# RelayController.net
KiCad netlist of a schematic drawn in Altium Designer
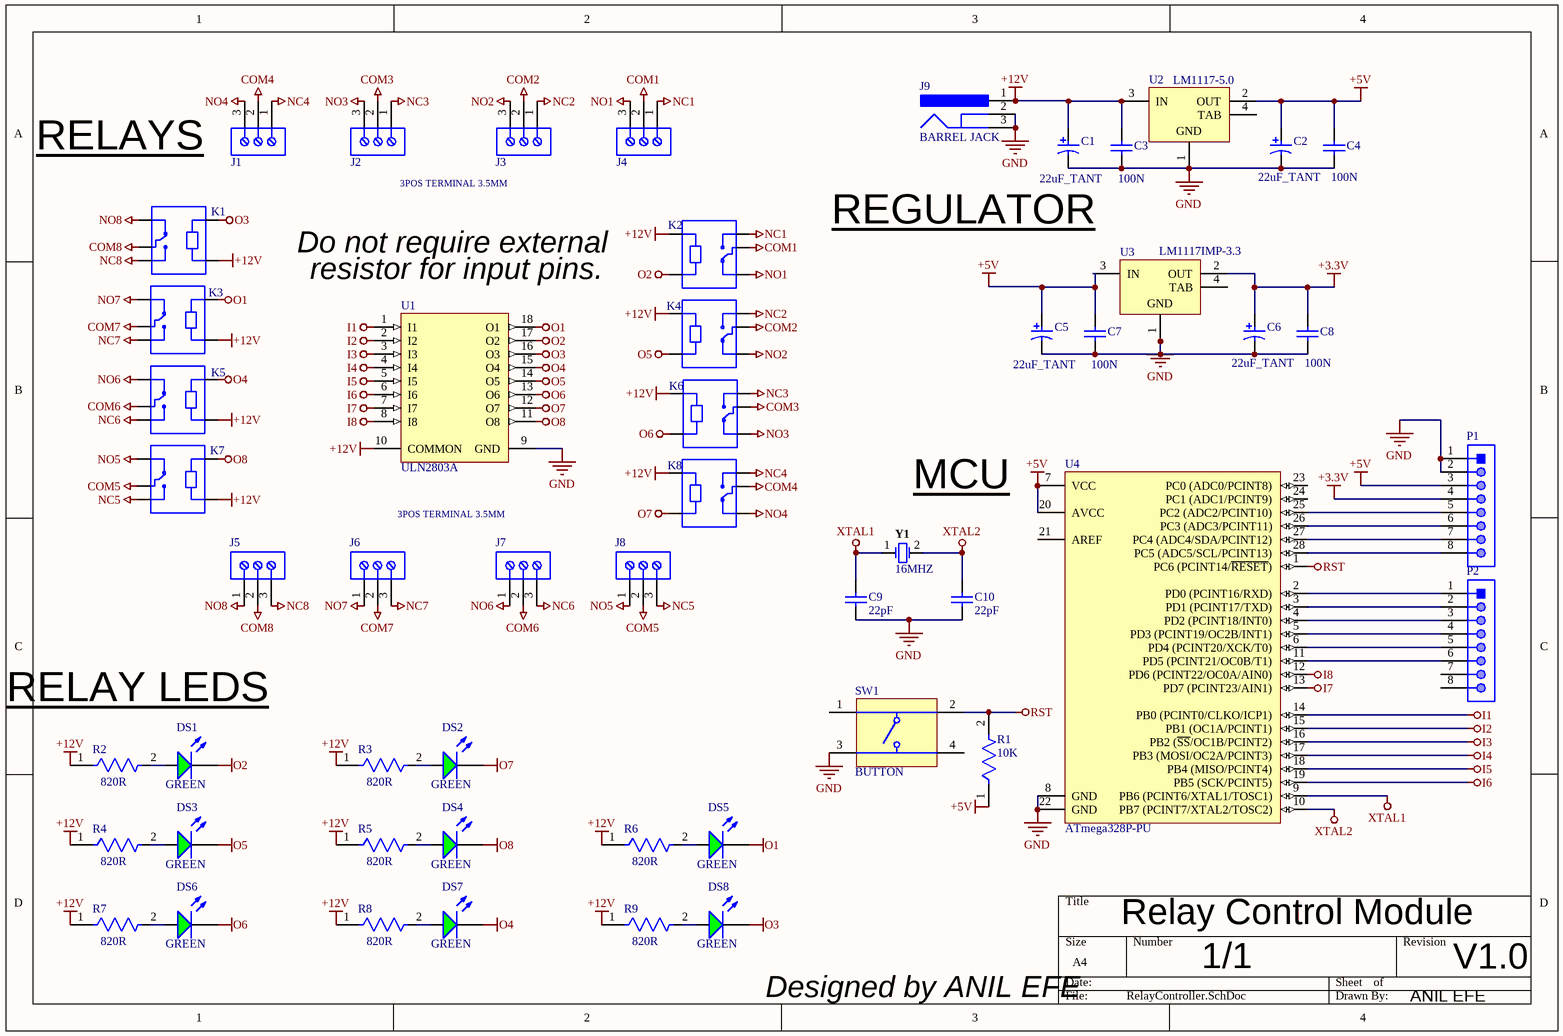
[diagram p0: RelayController.SchDoc]

(export (version "E")
  (design (tool "Eeschema 10.0.6"))
  (components
    (comp (ref "C1")
      (value "22uF_TANT")
      (footprint "KEMT-T491-D_L")
      (fields (field (name "MANUFACTURER") "Kemet"))
      (libsource (lib "Altium Content Vault") (part "CAP-P-2"))
    )
    (comp (ref "C2")
      (value "22uF_TANT")
      (footprint "KEMT-T491-D_L")
      (fields (field (name "MANUFACTURER") "Kemet"))
      (libsource (lib "Altium Content Vault") (part "CAP-P-2"))
    )
    (comp (ref "C3")
      (value "100N")
      (footprint "KEMT-1206-2_M")
      (description "CAP, Ceramic, 0.1 uF, +/- 10%, 50 V, -55 to 125 degC, 1206 (3216 Metric), RoHS, Tape and Reel")
      (fields (field (name "MANUFACTURER") "Kemet"))
      (libsource (lib "Altium Content Vault") (part "CAP-NP-2"))
    )
    (comp (ref "C4")
      (value "100N")
      (footprint "KEMT-1206-2_M")
      (description "CAP, Ceramic, 0.1 uF, +/- 10%, 50 V, -55 to 125 degC, 1206 (3216 Metric), RoHS, Tape and Reel")
      (fields (field (name "MANUFACTURER") "Kemet"))
      (libsource (lib "Altium Content Vault") (part "CAP-NP-2"))
    )
    (comp (ref "C5")
      (value "22uF_TANT")
      (footprint "KEMT-T491-D_L")
      (fields (field (name "MANUFACTURER") "Kemet"))
      (libsource (lib "Altium Content Vault") (part "CAP-P-2"))
    )
    (comp (ref "C6")
      (value "22uF_TANT")
      (footprint "KEMT-T491-D_L")
      (fields (field (name "MANUFACTURER") "Kemet"))
      (libsource (lib "Altium Content Vault") (part "CAP-P-2"))
    )
    (comp (ref "C7")
      (value "100N")
      (footprint "KEMT-1206-2_M")
      (description "CAP, Ceramic, 0.1 uF, +/- 10%, 50 V, -55 to 125 degC, 1206 (3216 Metric), RoHS, Tape and Reel")
      (fields (field (name "MANUFACTURER") "Kemet"))
      (libsource (lib "Altium Content Vault") (part "CAP-NP-2"))
    )
    (comp (ref "C8")
      (value "100N")
      (footprint "KEMT-1206-2_M")
      (description "CAP, Ceramic, 0.1 uF, +/- 10%, 50 V, -55 to 125 degC, 1206 (3216 Metric), RoHS, Tape and Reel")
      (fields (field (name "MANUFACTURER") "Kemet"))
      (libsource (lib "Altium Content Vault") (part "CAP-NP-2"))
    )
    (comp (ref "C9")
      (value "22pF")
      (footprint "KEMT-1206-2_M")
      (description "CAP, Ceramic, 0.1 uF, +/- 10%, 50 V, -55 to 125 degC, 1206 (3216 Metric), RoHS, Tape and Reel")
      (fields (field (name "MANUFACTURER") "Kemet"))
      (libsource (lib "Altium Content Vault") (part "CAP-NP-2"))
    )
    (comp (ref "C10")
      (value "22pF")
      (footprint "KEMT-1206-2_M")
      (description "CAP, Ceramic, 0.1 uF, +/- 10%, 50 V, -55 to 125 degC, 1206 (3216 Metric), RoHS, Tape and Reel")
      (fields (field (name "MANUFACTURER") "Kemet"))
      (libsource (lib "Altium Content Vault") (part "CAP-NP-2"))
    )
    (comp (ref "DS1")
      (value "GREEN")
      (footprint "KING-APTD3216CGCK_V")
      (description "Chip LED Lamp, Green, 5 V, 30 mA, -40 to 85 degC, 2-Pin SMD, RoHS, Tape and Reel")
      (fields (field (name "MANUFACTURER") "Kingbright"))
      (libsource (lib "Altium Content Vault") (part "LED-GREEN-AK-2"))
    )
    (comp (ref "DS2")
      (value "GREEN")
      (footprint "KING-APTD3216CGCK_V")
      (description "Chip LED Lamp, Green, 5 V, 30 mA, -40 to 85 degC, 2-Pin SMD, RoHS, Tape and Reel")
      (fields (field (name "MANUFACTURER") "Kingbright"))
      (libsource (lib "Altium Content Vault") (part "LED-GREEN-AK-2"))
    )
    (comp (ref "DS3")
      (value "GREEN")
      (footprint "KING-APTD3216CGCK_V")
      (description "Chip LED Lamp, Green, 5 V, 30 mA, -40 to 85 degC, 2-Pin SMD, RoHS, Tape and Reel")
      (fields (field (name "MANUFACTURER") "Kingbright"))
      (libsource (lib "Altium Content Vault") (part "LED-GREEN-AK-2"))
    )
    (comp (ref "DS4")
      (value "GREEN")
      (footprint "KING-APTD3216CGCK_V")
      (description "Chip LED Lamp, Green, 5 V, 30 mA, -40 to 85 degC, 2-Pin SMD, RoHS, Tape and Reel")
      (fields (field (name "MANUFACTURER") "Kingbright"))
      (libsource (lib "Altium Content Vault") (part "LED-GREEN-AK-2"))
    )
    (comp (ref "DS5")
      (value "GREEN")
      (footprint "KING-APTD3216CGCK_V")
      (description "Chip LED Lamp, Green, 5 V, 30 mA, -40 to 85 degC, 2-Pin SMD, RoHS, Tape and Reel")
      (fields (field (name "MANUFACTURER") "Kingbright"))
      (libsource (lib "Altium Content Vault") (part "LED-GREEN-AK-2"))
    )
    (comp (ref "DS6")
      (value "GREEN")
      (footprint "KING-APTD3216CGCK_V")
      (description "Chip LED Lamp, Green, 5 V, 30 mA, -40 to 85 degC, 2-Pin SMD, RoHS, Tape and Reel")
      (fields (field (name "MANUFACTURER") "Kingbright"))
      (libsource (lib "Altium Content Vault") (part "LED-GREEN-AK-2"))
    )
    (comp (ref "DS7")
      (value "GREEN")
      (footprint "KING-APTD3216CGCK_V")
      (description "Chip LED Lamp, Green, 5 V, 30 mA, -40 to 85 degC, 2-Pin SMD, RoHS, Tape and Reel")
      (fields (field (name "MANUFACTURER") "Kingbright"))
      (libsource (lib "Altium Content Vault") (part "LED-GREEN-AK-2"))
    )
    (comp (ref "DS8")
      (value "GREEN")
      (footprint "KING-APTD3216CGCK_V")
      (description "Chip LED Lamp, Green, 5 V, 30 mA, -40 to 85 degC, 2-Pin SMD, RoHS, Tape and Reel")
      (fields (field (name "MANUFACTURER") "Kingbright"))
      (libsource (lib "Altium Content Vault") (part "LED-GREEN-AK-2"))
    )
    (comp (ref "J1")
      (value "691214110003")
      (footprint "691214110003")
      (description "Serie 2141 - 3.50 mm Horizontal Entry Modular with Rising Cage Clamp WR-TBL, 3 pin")
      (fields (field (name "MANUFACTURER") "Wurth Elektronik") (field (name "PUBLISHER") "WurthElektronik"))
      (libsource (lib "Altium Content Vault") (part "WE-CN-1P-F-TB3"))
    )
    (comp (ref "J2")
      (value "691214110003")
      (footprint "691214110003")
      (description "Serie 2141 - 3.50 mm Horizontal Entry Modular with Rising Cage Clamp WR-TBL, 3 pin")
      (fields (field (name "MANUFACTURER") "Wurth Elektronik") (field (name "PUBLISHER") "WurthElektronik"))
      (libsource (lib "Altium Content Vault") (part "WE-CN-1P-F-TB3"))
    )
    (comp (ref "J3")
      (value "3POS TERMINAL 3.5MM")
      (footprint "691214110003")
      (description "Serie 2141 - 3.50 mm Horizontal Entry Modular with Rising Cage Clamp WR-TBL, 3 pin")
      (fields
        (field (name "MANUFACTURER") "Wurth Elektronik")
        (field (name "PART NUMBER") "691214110003")
        (field (name "PUBLISHER") "WurthElektronik")
      )
      (libsource (lib "Altium Content Vault") (part "WE-CN-1P-F-TB3"))
    )
    (comp (ref "J4")
      (value "691214110003")
      (footprint "691214110003")
      (description "Serie 2141 - 3.50 mm Horizontal Entry Modular with Rising Cage Clamp WR-TBL, 3 pin")
      (fields (field (name "MANUFACTURER") "Wurth Elektronik") (field (name "PUBLISHER") "WurthElektronik"))
      (libsource (lib "Altium Content Vault") (part "WE-CN-1P-F-TB3"))
    )
    (comp (ref "J5")
      (value "691214110003")
      (footprint "691214110003")
      (description "Serie 2141 - 3.50 mm Horizontal Entry Modular with Rising Cage Clamp WR-TBL, 3 pin")
      (fields (field (name "MANUFACTURER") "Wurth Elektronik") (field (name "PUBLISHER") "WurthElektronik"))
      (libsource (lib "Altium Content Vault") (part "WE-CN-1P-F-TB3"))
    )
    (comp (ref "J6")
      (value "3POS TERMINAL 3.5MM")
      (footprint "691214110003")
      (description "Serie 2141 - 3.50 mm Horizontal Entry Modular with Rising Cage Clamp WR-TBL, 3 pin")
      (fields
        (field (name "MANUFACTURER") "Wurth Elektronik")
        (field (name "PART NUMBER") "691214110003")
        (field (name "PUBLISHER") "WurthElektronik")
      )
      (libsource (lib "Altium Content Vault") (part "WE-CN-1P-F-TB3"))
    )
    (comp (ref "J7")
      (value "691214110003")
      (footprint "691214110003")
      (description "Serie 2141 - 3.50 mm Horizontal Entry Modular with Rising Cage Clamp WR-TBL, 3 pin")
      (fields (field (name "MANUFACTURER") "Wurth Elektronik") (field (name "PUBLISHER") "WurthElektronik"))
      (libsource (lib "Altium Content Vault") (part "WE-CN-1P-F-TB3"))
    )
    (comp (ref "J8")
      (value "691214110003")
      (footprint "691214110003")
      (description "Serie 2141 - 3.50 mm Horizontal Entry Modular with Rising Cage Clamp WR-TBL, 3 pin")
      (fields (field (name "MANUFACTURER") "Wurth Elektronik") (field (name "PUBLISHER") "WurthElektronik"))
      (libsource (lib "Altium Content Vault") (part "WE-CN-1P-F-TB3"))
    )
    (comp (ref "J9")
      (value "BARREL JACK")
      (footprint "CUI-PJ-002AH-4_V")
      (description "DC Power Jack, Right Angle, -25 to 85 degC, 4-Pin 14.8 x 9 x 11 mm SMD, RoHS, Tape and Reel")
      (fields (field (name "MANUFACTURER") "CUIInc.") (field (name "PARTNUMBER") "PJ-002AH"))
      (libsource (lib "Altium Content Vault") (part "JACK-2CD3-RN"))
    )
    (comp (ref "K1")
      (value "SRD-05VDC-SL-C")
      (footprint "RELAY_SRD-05VDC-SL-C")
      (fields (field (name "MF") "Songle Relay"))
      (libsource (lib "SRD-05VDC-SL-C") (part "SRD-05VDC-SL-C"))
    )
    (comp (ref "K2")
      (value "SRD-05VDC-SL-C")
      (footprint "RELAY_SRD-05VDC-SL-C")
      (fields (field (name "MF") "Songle Relay"))
      (libsource (lib "SRD-05VDC-SL-C") (part "SRD-05VDC-SL-C"))
    )
    (comp (ref "K3")
      (value "SRD-05VDC-SL-C")
      (footprint "RELAY_SRD-05VDC-SL-C")
      (fields (field (name "MF") "Songle Relay"))
      (libsource (lib "SRD-05VDC-SL-C") (part "SRD-05VDC-SL-C"))
    )
    (comp (ref "K4")
      (value "~")
      (footprint "RELAY_SRD-05VDC-SL-C")
      (fields (field (name "MP") "SRD-05VDC-SL-C") (field (name "MF") "Songle Relay"))
      (libsource (lib "SRD-05VDC-SL-C") (part "SRD-05VDC-SL-C"))
    )
    (comp (ref "K5")
      (value "SRD-05VDC-SL-C")
      (footprint "RELAY_SRD-05VDC-SL-C")
      (fields (field (name "MF") "Songle Relay"))
      (libsource (lib "SRD-05VDC-SL-C") (part "SRD-05VDC-SL-C"))
    )
    (comp (ref "K6")
      (value "SRD-05VDC-SL-C")
      (footprint "RELAY_SRD-05VDC-SL-C")
      (fields (field (name "MF") "Songle Relay"))
      (libsource (lib "SRD-05VDC-SL-C") (part "SRD-05VDC-SL-C"))
    )
    (comp (ref "K7")
      (value "SRD-05VDC-SL-C")
      (footprint "RELAY_SRD-05VDC-SL-C")
      (fields (field (name "MF") "Songle Relay"))
      (libsource (lib "SRD-05VDC-SL-C") (part "SRD-05VDC-SL-C"))
    )
    (comp (ref "K8")
      (value "SRD-05VDC-SL-C")
      (footprint "RELAY_SRD-05VDC-SL-C")
      (fields (field (name "MF") "Songle Relay"))
      (libsource (lib "SRD-05VDC-SL-C") (part "SRD-05VDC-SL-C"))
    )
    (comp (ref "P1")
      (value "66200811122")
      (footprint "66200811122")
      (description "THT Male Header WR-MPC3, Vertical, Single Row, pitch 3 mm, 8 pins")
      (fields (field (name "MANUFACTURER") "Wurth Elektronik") (field (name "PUBLISHER") "WurthElektronik"))
      (libsource (lib "Altium Content Vault") (part "WE-CN-1P-M-R8"))
    )
    (comp (ref "P2")
      (value "66200811122")
      (footprint "66200811122")
      (description "THT Male Header WR-MPC3, Vertical, Single Row, pitch 3 mm, 8 pins")
      (fields (field (name "MANUFACTURER") "Wurth Elektronik") (field (name "PUBLISHER") "WurthElektronik"))
      (libsource (lib "Altium Content Vault") (part "WE-CN-1P-M-R8"))
    )
    (comp (ref "R1")
      (value "10K")
      (footprint "FP-RC1206-MFG")
      (description "RES SMD 0 OHM JUMPER 1/4W 1206")
      (fields
        (field (name "MANUFACTURER PART NUMBER") "RC1206JR-070RL")
        (field (name "MANUFACTURER") "YAGEO")
      )
      (libsource (lib "Altium Content Vault") (part "1029c3af85768c4190bb7ad29bc67b5"))
    )
    (comp (ref "R2")
      (value "820R")
      (footprint "FP-RC1206-MFG")
      (description "RES SMD 0 OHM JUMPER 1/4W 1206")
      (fields
        (field (name "MANUFACTURER PART NUMBER") "RC1206JR-070RL")
        (field (name "MANUFACTURER") "YAGEO")
      )
      (libsource (lib "Altium Content Vault") (part "1029c3af85768c4190bb7ad29bc67b5"))
    )
    (comp (ref "R3")
      (value "820R")
      (footprint "FP-RC1206-MFG")
      (description "RES SMD 0 OHM JUMPER 1/4W 1206")
      (fields
        (field (name "MANUFACTURER PART NUMBER") "RC1206JR-070RL")
        (field (name "MANUFACTURER") "YAGEO")
      )
      (libsource (lib "Altium Content Vault") (part "1029c3af85768c4190bb7ad29bc67b5"))
    )
    (comp (ref "R4")
      (value "820R")
      (footprint "FP-RC1206-MFG")
      (description "RES SMD 0 OHM JUMPER 1/4W 1206")
      (fields
        (field (name "MANUFACTURER PART NUMBER") "RC1206JR-070RL")
        (field (name "MANUFACTURER") "YAGEO")
      )
      (libsource (lib "Altium Content Vault") (part "1029c3af85768c4190bb7ad29bc67b5"))
    )
    (comp (ref "R5")
      (value "820R")
      (footprint "FP-RC1206-MFG")
      (description "RES SMD 0 OHM JUMPER 1/4W 1206")
      (fields
        (field (name "MANUFACTURER PART NUMBER") "RC1206JR-070RL")
        (field (name "MANUFACTURER") "YAGEO")
      )
      (libsource (lib "Altium Content Vault") (part "1029c3af85768c4190bb7ad29bc67b5"))
    )
    (comp (ref "R6")
      (value "820R")
      (footprint "FP-RC1206-MFG")
      (description "RES SMD 0 OHM JUMPER 1/4W 1206")
      (fields
        (field (name "MANUFACTURER PART NUMBER") "RC1206JR-070RL")
        (field (name "MANUFACTURER") "YAGEO")
      )
      (libsource (lib "Altium Content Vault") (part "1029c3af85768c4190bb7ad29bc67b5"))
    )
    (comp (ref "R7")
      (value "820R")
      (footprint "FP-RC1206-MFG")
      (description "RES SMD 0 OHM JUMPER 1/4W 1206")
      (fields
        (field (name "MANUFACTURER PART NUMBER") "RC1206JR-070RL")
        (field (name "MANUFACTURER") "YAGEO")
      )
      (libsource (lib "Altium Content Vault") (part "1029c3af85768c4190bb7ad29bc67b5"))
    )
    (comp (ref "R8")
      (value "820R")
      (footprint "FP-RC1206-MFG")
      (description "RES SMD 0 OHM JUMPER 1/4W 1206")
      (fields
        (field (name "MANUFACTURER PART NUMBER") "RC1206JR-070RL")
        (field (name "MANUFACTURER") "YAGEO")
      )
      (libsource (lib "Altium Content Vault") (part "1029c3af85768c4190bb7ad29bc67b5"))
    )
    (comp (ref "R9")
      (value "820R")
      (footprint "FP-RC1206-MFG")
      (description "RES SMD 0 OHM JUMPER 1/4W 1206")
      (fields
        (field (name "MANUFACTURER PART NUMBER") "RC1206JR-070RL")
        (field (name "MANUFACTURER") "YAGEO")
      )
      (libsource (lib "Altium Content Vault") (part "1029c3af85768c4190bb7ad29bc67b5"))
    )
    (comp (ref "SW1")
      (value "BUTTON")
      (footprint "TECO-FSM4JSMATR_V")
      (description "Micro Miniature Push Button Switch FSM JSM, 50 mA, -35 to 85 degC, 4-Pin SMD, RoHS, Tape and Reel")
      (fields (field (name "MANUFACTURER") "TE Connectivity"))
      (libsource (lib "Altium Content Vault") (part "SW-SPST-4_A"))
    )
    (comp (ref "U1")
      (value "ULN2803A")
      (footprint "STM-DIP-18")
      (description "Eight Darlington Arrays, 50 V, 2.25 W, 500 mA, 18-Pin DIP, RoHS, Tube")
      (fields (field (name "MANUFACTURER") "STMicroelectronics"))
      (libsource (lib "Altium Content Vault") (part "TOSH-ULN2803_04-DIP-18"))
    )
    (comp (ref "U2")
      (value "LM1117-5.0")
      (footprint "DCY0004A_M")
      (description "800mA Low-Dropout Linear Regulator, 4-pin SOT-223, Pb-Free")
      (fields
        (field (name "MANUFACTURER") "Texas Instruments")
        (field (name "PARTNUMBER") "LM1117IMP-5.0/NOPB")
      )
      (libsource (lib "Altium Content Vault") (part "PM-REG-LM1086-SOT4"))
    )
    (comp (ref "U3")
      (value "LM1117IMP-3.3")
      (footprint "DCY0004A_N")
      (description "800mA Low-Dropout Linear Regulator, 4-pin SOT-223, Pb-Free")
      (fields
        (field (name "PARTNUMBER") "LM1117IMP-3.3/NOPB")
        (field (name "MANUFACTURER") "Texas Instruments")
      )
      (libsource (lib "Altium Content Vault") (part "PM-REG-LM1086-SOT4"))
    )
    (comp (ref "U4")
      (value "ATmega328P-PU")
      (footprint "28P3")
      (libsource (lib "Altium Content Vault") (part "MC-8B-ATM48-IL28"))
    )
    (comp (ref "Y1")
      (value "16MHZ")
      (footprint "FOX-FOXSLF-2_V")
      (description "Resistance Weld Thru-Hole Crystal, 12 MHz, +/-30 ppm, -20 to 70 degC, 2-Pin THD, RoHS, Bulk")
      (libsource (lib "Altium Content Vault") (part "XTAL-1-2-2"))
    )
  )
  (nets
    (net (code "1") (name "+3.3V") (class "Default")
      (node (ref "C6") (pin "1") (pinfunction "1_1") (pintype "passive"))
      (node (ref "C8") (pin "2") (pinfunction "2_2") (pintype "passive"))
      (node (ref "P1") (pin "4") (pinfunction "4_4") (pintype "passive"))
      (node (ref "U3") (pin "2") (pinfunction "OUT_2") (pintype "power_in"))
    )
    (net (code "2") (name "+5V") (class "Default")
      (node (ref "C2") (pin "1") (pinfunction "1_1") (pintype "passive"))
      (node (ref "C4") (pin "2") (pinfunction "2_2") (pintype "passive"))
      (node (ref "C5") (pin "1") (pinfunction "1_1") (pintype "passive"))
      (node (ref "C7") (pin "2") (pinfunction "2_2") (pintype "passive"))
      (node (ref "P1") (pin "3") (pinfunction "3_3") (pintype "passive"))
      (node (ref "R1") (pin "1") (pinfunction "1_1") (pintype "passive"))
      (node (ref "U2") (pin "2") (pinfunction "OUT_2") (pintype "power_in"))
      (node (ref "U3") (pin "3") (pinfunction "IN_3") (pintype "power_in"))
      (node (ref "U4") (pin "20") (pinfunction "AVCC_20") (pintype "power_in"))
      (node (ref "U4") (pin "7") (pinfunction "VCC_7") (pintype "power_in"))
    )
    (net (code "3") (name "+12V") (class "Default")
      (node (ref "C1") (pin "1") (pinfunction "1_1") (pintype "passive"))
      (node (ref "C3") (pin "2") (pinfunction "2_2") (pintype "passive"))
      (node (ref "J9") (pin "1") (pinfunction "1_1") (pintype "passive"))
      (node (ref "K1") (pin "A1") (pinfunction "A1_A1") (pintype "passive"))
      (node (ref "K2") (pin "A1") (pinfunction "A1_A1") (pintype "passive"))
      (node (ref "K3") (pin "A1") (pinfunction "A1_A1") (pintype "passive"))
      (node (ref "K4") (pin "A1") (pinfunction "A1_A1") (pintype "passive"))
      (node (ref "K5") (pin "A1") (pinfunction "A1_A1") (pintype "passive"))
      (node (ref "K6") (pin "A1") (pinfunction "A1_A1") (pintype "passive"))
      (node (ref "K7") (pin "A1") (pinfunction "A1_A1") (pintype "passive"))
      (node (ref "K8") (pin "A1") (pinfunction "A1_A1") (pintype "passive"))
      (node (ref "R2") (pin "1") (pinfunction "1_1") (pintype "passive"))
      (node (ref "R3") (pin "1") (pinfunction "1_1") (pintype "passive"))
      (node (ref "R4") (pin "1") (pinfunction "1_1") (pintype "passive"))
      (node (ref "R5") (pin "1") (pinfunction "1_1") (pintype "passive"))
      (node (ref "R6") (pin "1") (pinfunction "1_1") (pintype "passive"))
      (node (ref "R7") (pin "1") (pinfunction "1_1") (pintype "passive"))
      (node (ref "R8") (pin "1") (pinfunction "1_1") (pintype "passive"))
      (node (ref "R9") (pin "1") (pinfunction "1_1") (pintype "passive"))
      (node (ref "U1") (pin "10") (pinfunction "COMMON_10") (pintype "passive"))
      (node (ref "U2") (pin "3") (pinfunction "IN_3") (pintype "power_in"))
    )
    (net (code "4") (name "COM1") (class "Default")
      (node (ref "J4") (pin "2") (pinfunction "2_2") (pintype "passive"))
      (node (ref "K2") (pin "COM") (pinfunction "COM_COM") (pintype "passive"))
    )
    (net (code "5") (name "COM2") (class "Default")
      (node (ref "J3") (pin "2") (pinfunction "2_2") (pintype "passive"))
      (node (ref "K4") (pin "COM") (pinfunction "COM_COM") (pintype "passive"))
    )
    (net (code "6") (name "COM3") (class "Default")
      (node (ref "J2") (pin "2") (pinfunction "2_2") (pintype "passive"))
      (node (ref "K6") (pin "COM") (pinfunction "COM_COM") (pintype "passive"))
    )
    (net (code "7") (name "COM4") (class "Default")
      (node (ref "J1") (pin "2") (pinfunction "2_2") (pintype "passive"))
      (node (ref "K8") (pin "COM") (pinfunction "COM_COM") (pintype "passive"))
    )
    (net (code "8") (name "COM5") (class "Default")
      (node (ref "J8") (pin "2") (pinfunction "2_2") (pintype "passive"))
      (node (ref "K7") (pin "COM") (pinfunction "COM_COM") (pintype "passive"))
    )
    (net (code "9") (name "COM6") (class "Default")
      (node (ref "J7") (pin "2") (pinfunction "2_2") (pintype "passive"))
      (node (ref "K5") (pin "COM") (pinfunction "COM_COM") (pintype "passive"))
    )
    (net (code "10") (name "COM7") (class "Default")
      (node (ref "J6") (pin "2") (pinfunction "2_2") (pintype "passive"))
      (node (ref "K3") (pin "COM") (pinfunction "COM_COM") (pintype "passive"))
    )
    (net (code "11") (name "COM8") (class "Default")
      (node (ref "J5") (pin "2") (pinfunction "2_2") (pintype "passive"))
      (node (ref "K1") (pin "COM") (pinfunction "COM_COM") (pintype "passive"))
    )
    (net (code "12") (name "GND") (class "Default")
      (node (ref "C1") (pin "2") (pinfunction "2_2") (pintype "passive"))
      (node (ref "C10") (pin "1") (pinfunction "1_1") (pintype "passive"))
      (node (ref "C2") (pin "2") (pinfunction "2_2") (pintype "passive"))
      (node (ref "C3") (pin "1") (pinfunction "1_1") (pintype "passive"))
      (node (ref "C4") (pin "1") (pinfunction "1_1") (pintype "passive"))
      (node (ref "C5") (pin "2") (pinfunction "2_2") (pintype "passive"))
      (node (ref "C6") (pin "2") (pinfunction "2_2") (pintype "passive"))
      (node (ref "C7") (pin "1") (pinfunction "1_1") (pintype "passive"))
      (node (ref "C8") (pin "1") (pinfunction "1_1") (pintype "passive"))
      (node (ref "C9") (pin "1") (pinfunction "1_1") (pintype "passive"))
      (node (ref "J9") (pin "2") (pinfunction "2_2") (pintype "passive"))
      (node (ref "J9") (pin "3") (pinfunction "3_3") (pintype "passive"))
      (node (ref "P1") (pin "1") (pinfunction "1_1") (pintype "passive"))
      (node (ref "P1") (pin "2") (pinfunction "2_2") (pintype "passive"))
      (node (ref "SW1") (pin "3") (pinfunction "3_3") (pintype "passive"))
      (node (ref "U1") (pin "9") (pinfunction "GND_9") (pintype "power_in"))
      (node (ref "U2") (pin "1") (pinfunction "GND_1") (pintype "power_in"))
      (node (ref "U3") (pin "1") (pinfunction "GND_1") (pintype "power_in"))
      (node (ref "U4") (pin "22") (pinfunction "GND_22") (pintype "power_in"))
      (node (ref "U4") (pin "8") (pinfunction "GND_8") (pintype "power_in"))
    )
    (net (code "13") (name "I1") (class "Default")
      (node (ref "U1") (pin "1") (pinfunction "I1_1") (pintype "input"))
      (node (ref "U4") (pin "14") (pinfunction "PB0_(PCINT0/CLKO/ICP1)_14") (pintype "bidirectional"))
    )
    (net (code "14") (name "I2") (class "Default")
      (node (ref "U1") (pin "2") (pinfunction "I2_2") (pintype "input"))
      (node (ref "U4") (pin "15") (pinfunction "PB1_(OC1A/PCINT1)_15") (pintype "bidirectional"))
    )
    (net (code "15") (name "I3") (class "Default")
      (node (ref "U1") (pin "3") (pinfunction "I3_3") (pintype "input"))
      (node (ref "U4") (pin "16") (pinfunction "PB2_(~{SS}/OC1B/PCINT2)_16") (pintype "bidirectional"))
    )
    (net (code "16") (name "I4") (class "Default")
      (node (ref "U1") (pin "4") (pinfunction "I4_4") (pintype "input"))
      (node (ref "U4") (pin "17") (pinfunction "PB3_(MOSI/OC2A/PCINT3)_17") (pintype "bidirectional"))
    )
    (net (code "17") (name "I5") (class "Default")
      (node (ref "U1") (pin "5") (pinfunction "I5_5") (pintype "input"))
      (node (ref "U4") (pin "18") (pinfunction "PB4_(MISO/PCINT4)_18") (pintype "bidirectional"))
    )
    (net (code "18") (name "I6") (class "Default")
      (node (ref "U1") (pin "6") (pinfunction "I6_6") (pintype "input"))
      (node (ref "U4") (pin "19") (pinfunction "PB5_(SCK/PCINT5)_19") (pintype "bidirectional"))
    )
    (net (code "19") (name "I7") (class "Default")
      (node (ref "U1") (pin "7") (pinfunction "I7_7") (pintype "input"))
      (node (ref "U4") (pin "13") (pinfunction "PD7_(PCINT23/AIN1)_13") (pintype "bidirectional"))
    )
    (net (code "20") (name "I8") (class "Default")
      (node (ref "U1") (pin "8") (pinfunction "I8_8") (pintype "input"))
      (node (ref "U4") (pin "12") (pinfunction "PD6_(PCINT22/OC0A/AIN0)_12") (pintype "bidirectional"))
    )
    (net (code "21") (name "NC1") (class "Default")
      (node (ref "J4") (pin "1") (pinfunction "1_1") (pintype "passive"))
      (node (ref "K2") (pin "NO") (pinfunction "NO_NO") (pintype "passive"))
    )
    (net (code "22") (name "NC2") (class "Default")
      (node (ref "J3") (pin "1") (pinfunction "1_1") (pintype "passive"))
      (node (ref "K4") (pin "NO") (pinfunction "NO_NO") (pintype "passive"))
    )
    (net (code "23") (name "NC3") (class "Default")
      (node (ref "J2") (pin "1") (pinfunction "1_1") (pintype "passive"))
      (node (ref "K6") (pin "NO") (pinfunction "NO_NO") (pintype "passive"))
    )
    (net (code "24") (name "NC4") (class "Default")
      (node (ref "J1") (pin "1") (pinfunction "1_1") (pintype "passive"))
      (node (ref "K8") (pin "NO") (pinfunction "NO_NO") (pintype "passive"))
    )
    (net (code "25") (name "NC5") (class "Default")
      (node (ref "J8") (pin "3") (pinfunction "3_3") (pintype "passive"))
      (node (ref "K7") (pin "NO") (pinfunction "NO_NO") (pintype "passive"))
    )
    (net (code "26") (name "NC6") (class "Default")
      (node (ref "J7") (pin "3") (pinfunction "3_3") (pintype "passive"))
      (node (ref "K5") (pin "NO") (pinfunction "NO_NO") (pintype "passive"))
    )
    (net (code "27") (name "NC7") (class "Default")
      (node (ref "J6") (pin "3") (pinfunction "3_3") (pintype "passive"))
      (node (ref "K3") (pin "NO") (pinfunction "NO_NO") (pintype "passive"))
    )
    (net (code "28") (name "NC8") (class "Default")
      (node (ref "J5") (pin "3") (pinfunction "3_3") (pintype "passive"))
      (node (ref "K1") (pin "NO") (pinfunction "NO_NO") (pintype "passive"))
    )
    (net (code "29") (name "NO1") (class "Default")
      (node (ref "J4") (pin "3") (pinfunction "3_3") (pintype "passive"))
      (node (ref "K2") (pin "NC") (pinfunction "NC_NC") (pintype "passive"))
    )
    (net (code "30") (name "NO2") (class "Default")
      (node (ref "J3") (pin "3") (pinfunction "3_3") (pintype "passive"))
      (node (ref "K4") (pin "NC") (pinfunction "NC_NC") (pintype "passive"))
    )
    (net (code "31") (name "NO3") (class "Default")
      (node (ref "J2") (pin "3") (pinfunction "3_3") (pintype "passive"))
      (node (ref "K6") (pin "NC") (pinfunction "NC_NC") (pintype "passive"))
    )
    (net (code "32") (name "NO4") (class "Default")
      (node (ref "J1") (pin "3") (pinfunction "3_3") (pintype "passive"))
      (node (ref "K8") (pin "NC") (pinfunction "NC_NC") (pintype "passive"))
    )
    (net (code "33") (name "NO5") (class "Default")
      (node (ref "J8") (pin "1") (pinfunction "1_1") (pintype "passive"))
      (node (ref "K7") (pin "NC") (pinfunction "NC_NC") (pintype "passive"))
    )
    (net (code "34") (name "NO6") (class "Default")
      (node (ref "J7") (pin "1") (pinfunction "1_1") (pintype "passive"))
      (node (ref "K5") (pin "NC") (pinfunction "NC_NC") (pintype "passive"))
    )
    (net (code "35") (name "NO7") (class "Default")
      (node (ref "J6") (pin "1") (pinfunction "1_1") (pintype "passive"))
      (node (ref "K3") (pin "NC") (pinfunction "NC_NC") (pintype "passive"))
    )
    (net (code "36") (name "NO8") (class "Default")
      (node (ref "J5") (pin "1") (pinfunction "1_1") (pintype "passive"))
      (node (ref "K1") (pin "NC") (pinfunction "NC_NC") (pintype "passive"))
    )
    (net (code "37") (name "Net-(DS1-A)") (class "Default")
      (node (ref "DS1") (pin "1") (pinfunction "A_1") (pintype "passive"))
      (node (ref "R2") (pin "2") (pinfunction "2_2") (pintype "passive"))
    )
    (net (code "38") (name "Net-(DS2-A)") (class "Default")
      (node (ref "DS2") (pin "1") (pinfunction "A_1") (pintype "passive"))
      (node (ref "R3") (pin "2") (pinfunction "2_2") (pintype "passive"))
    )
    (net (code "39") (name "Net-(DS3-A)") (class "Default")
      (node (ref "DS3") (pin "1") (pinfunction "A_1") (pintype "passive"))
      (node (ref "R4") (pin "2") (pinfunction "2_2") (pintype "passive"))
    )
    (net (code "40") (name "Net-(DS4-A)") (class "Default")
      (node (ref "DS4") (pin "1") (pinfunction "A_1") (pintype "passive"))
      (node (ref "R5") (pin "2") (pinfunction "2_2") (pintype "passive"))
    )
    (net (code "41") (name "Net-(DS5-A)") (class "Default")
      (node (ref "DS5") (pin "1") (pinfunction "A_1") (pintype "passive"))
      (node (ref "R6") (pin "2") (pinfunction "2_2") (pintype "passive"))
    )
    (net (code "42") (name "Net-(DS6-A)") (class "Default")
      (node (ref "DS6") (pin "1") (pinfunction "A_1") (pintype "passive"))
      (node (ref "R7") (pin "2") (pinfunction "2_2") (pintype "passive"))
    )
    (net (code "43") (name "Net-(DS7-A)") (class "Default")
      (node (ref "DS7") (pin "1") (pinfunction "A_1") (pintype "passive"))
      (node (ref "R8") (pin "2") (pinfunction "2_2") (pintype "passive"))
    )
    (net (code "44") (name "Net-(DS8-A)") (class "Default")
      (node (ref "DS8") (pin "1") (pinfunction "A_1") (pintype "passive"))
      (node (ref "R9") (pin "2") (pinfunction "2_2") (pintype "passive"))
    )
    (net (code "45") (name "Net-(U4-PC2_(ADC2{slash}PCINT10))") (class "Default")
      (node (ref "P1") (pin "5") (pinfunction "5_5") (pintype "passive"))
      (node (ref "U4") (pin "25") (pinfunction "PC2_(ADC2/PCINT10)_25") (pintype "bidirectional"))
    )
    (net (code "46") (name "Net-(U4-PC3_(ADC3{slash}PCINT11))") (class "Default")
      (node (ref "P1") (pin "6") (pinfunction "6_6") (pintype "passive"))
      (node (ref "U4") (pin "26") (pinfunction "PC3_(ADC3/PCINT11)_26") (pintype "bidirectional"))
    )
    (net (code "47") (name "Net-(U4-PC4_(ADC4{slash}SDA{slash}PCINT12))") (class "Default")
      (node (ref "P1") (pin "7") (pinfunction "7_7") (pintype "passive"))
      (node (ref "U4") (pin "27") (pinfunction "PC4_(ADC4/SDA/PCINT12)_27") (pintype "bidirectional"))
    )
    (net (code "48") (name "Net-(U4-PC5_(ADC5{slash}SCL{slash}PCINT13))") (class "Default")
      (node (ref "P1") (pin "8") (pinfunction "8_8") (pintype "passive"))
      (node (ref "U4") (pin "28") (pinfunction "PC5_(ADC5/SCL/PCINT13)_28") (pintype "bidirectional"))
    )
    (net (code "49") (name "Net-(U4-PD0_(PCINT16{slash}RXD))") (class "Default")
      (node (ref "P2") (pin "1") (pinfunction "1_1") (pintype "passive"))
      (node (ref "U4") (pin "2") (pinfunction "PD0_(PCINT16/RXD)_2") (pintype "bidirectional"))
    )
    (net (code "50") (name "Net-(U4-PD1_(PCINT17{slash}TXD))") (class "Default")
      (node (ref "P2") (pin "2") (pinfunction "2_2") (pintype "passive"))
      (node (ref "U4") (pin "3") (pinfunction "PD1_(PCINT17/TXD)_3") (pintype "bidirectional"))
    )
    (net (code "51") (name "Net-(U4-PD2_(PCINT18{slash}INT0))") (class "Default")
      (node (ref "P2") (pin "3") (pinfunction "3_3") (pintype "passive"))
      (node (ref "U4") (pin "4") (pinfunction "PD2_(PCINT18/INT0)_4") (pintype "bidirectional"))
    )
    (net (code "52") (name "Net-(U4-PD3_(PCINT19{slash}OC2B{slash}INT1))") (class "Default")
      (node (ref "P2") (pin "4") (pinfunction "4_4") (pintype "passive"))
      (node (ref "U4") (pin "5") (pinfunction "PD3_(PCINT19/OC2B/INT1)_5") (pintype "bidirectional"))
    )
    (net (code "53") (name "Net-(U4-PD4_(PCINT20{slash}XCK{slash}T0))") (class "Default")
      (node (ref "P2") (pin "5") (pinfunction "5_5") (pintype "passive"))
      (node (ref "U4") (pin "6") (pinfunction "PD4_(PCINT20/XCK/T0)_6") (pintype "bidirectional"))
    )
    (net (code "54") (name "Net-(U4-PD5_(PCINT21{slash}OC0B{slash}T1))") (class "Default")
      (node (ref "P2") (pin "6") (pinfunction "6_6") (pintype "passive"))
      (node (ref "U4") (pin "11") (pinfunction "PD5_(PCINT21/OC0B/T1)_11") (pintype "bidirectional"))
    )
    (net (code "55") (name "O1") (class "Default")
      (node (ref "DS5") (pin "2") (pinfunction "K_2") (pintype "passive"))
      (node (ref "K3") (pin "A2") (pinfunction "A2_A2") (pintype "passive"))
      (node (ref "U1") (pin "18") (pinfunction "O1_18") (pintype "output"))
    )
    (net (code "56") (name "O2") (class "Default")
      (node (ref "DS1") (pin "2") (pinfunction "K_2") (pintype "passive"))
      (node (ref "K2") (pin "A2") (pinfunction "A2_A2") (pintype "passive"))
      (node (ref "U1") (pin "17") (pinfunction "O2_17") (pintype "output"))
    )
    (net (code "57") (name "O3") (class "Default")
      (node (ref "DS8") (pin "2") (pinfunction "K_2") (pintype "passive"))
      (node (ref "K1") (pin "A2") (pinfunction "A2_A2") (pintype "passive"))
      (node (ref "U1") (pin "16") (pinfunction "O3_16") (pintype "output"))
    )
    (net (code "58") (name "O4") (class "Default")
      (node (ref "DS7") (pin "2") (pinfunction "K_2") (pintype "passive"))
      (node (ref "K5") (pin "A2") (pinfunction "A2_A2") (pintype "passive"))
      (node (ref "U1") (pin "15") (pinfunction "O4_15") (pintype "output"))
    )
    (net (code "59") (name "O5") (class "Default")
      (node (ref "DS3") (pin "2") (pinfunction "K_2") (pintype "passive"))
      (node (ref "K4") (pin "A2") (pinfunction "A2_A2") (pintype "passive"))
      (node (ref "U1") (pin "14") (pinfunction "O5_14") (pintype "output"))
    )
    (net (code "60") (name "O6") (class "Default")
      (node (ref "DS6") (pin "2") (pinfunction "K_2") (pintype "passive"))
      (node (ref "K6") (pin "A2") (pinfunction "A2_A2") (pintype "passive"))
      (node (ref "U1") (pin "13") (pinfunction "O6_13") (pintype "output"))
    )
    (net (code "61") (name "O7") (class "Default")
      (node (ref "DS2") (pin "2") (pinfunction "K_2") (pintype "passive"))
      (node (ref "K8") (pin "A2") (pinfunction "A2_A2") (pintype "passive"))
      (node (ref "U1") (pin "12") (pinfunction "O7_12") (pintype "output"))
    )
    (net (code "62") (name "O8") (class "Default")
      (node (ref "DS4") (pin "2") (pinfunction "K_2") (pintype "passive"))
      (node (ref "K7") (pin "A2") (pinfunction "A2_A2") (pintype "passive"))
      (node (ref "U1") (pin "11") (pinfunction "O8_11") (pintype "output"))
    )
    (net (code "63") (name "RST") (class "Default")
      (node (ref "R1") (pin "2") (pinfunction "2_2") (pintype "passive"))
      (node (ref "SW1") (pin "2") (pinfunction "2_2") (pintype "passive"))
      (node (ref "U4") (pin "1") (pinfunction "PC6_(PCINT14/~{RESET})_1") (pintype "bidirectional"))
    )
    (net (code "64") (name "XTAL1") (class "Default")
      (node (ref "C9") (pin "2") (pinfunction "2_2") (pintype "passive"))
      (node (ref "U4") (pin "9") (pinfunction "PB6_(PCINT6/XTAL1/TOSC1)_9") (pintype "bidirectional"))
      (node (ref "Y1") (pin "1") (pinfunction "1_1") (pintype "passive"))
    )
    (net (code "65") (name "XTAL2") (class "Default")
      (node (ref "C10") (pin "2") (pinfunction "2_2") (pintype "passive"))
      (node (ref "U4") (pin "10") (pinfunction "PB7_(PCINT7/XTAL2/TOSC2)_10") (pintype "bidirectional"))
      (node (ref "Y1") (pin "2") (pinfunction "2_2") (pintype "passive"))
    )
    (net (code "66") (name "unconnected-(P2-Pad7)") (class "Default")
      (node (ref "P2") (pin "7") (pinfunction "7_7") (pintype "passive"))
    )
    (net (code "67") (name "unconnected-(P2-Pad8)") (class "Default")
      (node (ref "P2") (pin "8") (pinfunction "8_8") (pintype "passive"))
    )
    (net (code "68") (name "unconnected-(SW1-Pad1)") (class "Default")
      (node (ref "SW1") (pin "1") (pinfunction "1_1") (pintype "passive"))
    )
    (net (code "69") (name "unconnected-(SW1-Pad4)") (class "Default")
      (node (ref "SW1") (pin "4") (pinfunction "4_4") (pintype "passive"))
    )
    (net (code "70") (name "unconnected-(U2-TAB-Pad4)") (class "Default")
      (node (ref "U2") (pin "4") (pinfunction "TAB_4") (pintype "power_in"))
    )
    (net (code "71") (name "unconnected-(U3-TAB-Pad4)") (class "Default")
      (node (ref "U3") (pin "4") (pinfunction "TAB_4") (pintype "power_in"))
    )
    (net (code "72") (name "unconnected-(U4-AREF-Pad21)") (class "Default")
      (node (ref "U4") (pin "21") (pinfunction "AREF_21") (pintype "power_in"))
    )
    (net (code "73") (name "unconnected-(U4-PC0_(ADC0{slash}PCINT8)-Pad23)") (class "Default")
      (node (ref "U4") (pin "23") (pinfunction "PC0_(ADC0/PCINT8)_23") (pintype "bidirectional"))
    )
    (net (code "74") (name "unconnected-(U4-PC1_(ADC1{slash}PCINT9)-Pad24)") (class "Default")
      (node (ref "U4") (pin "24") (pinfunction "PC1_(ADC1/PCINT9)_24") (pintype "bidirectional"))
    )
  )
)
